# through_hole.net
KiCad netlist of a schematic drawn in EAGLE
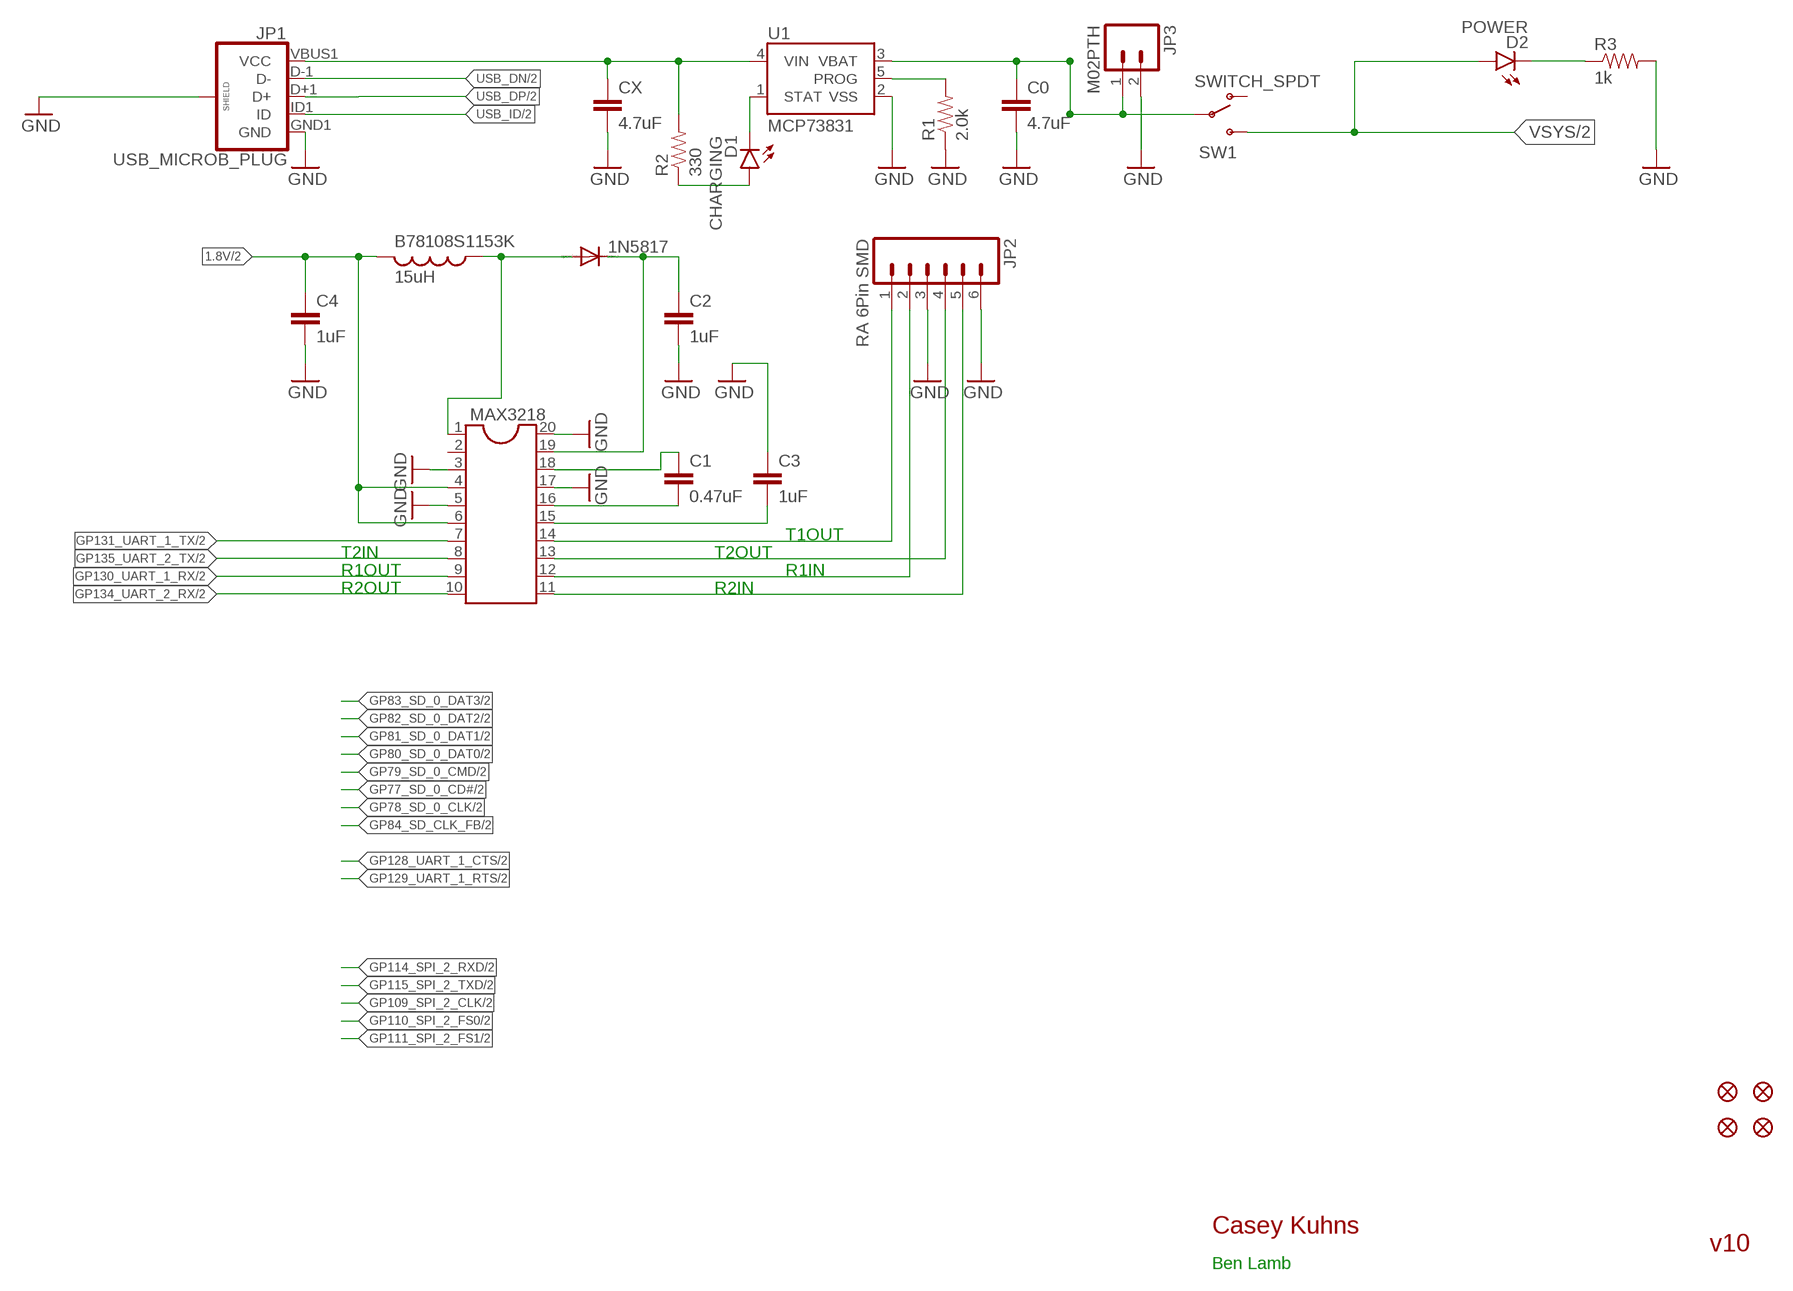
[diagram p0: schematic, sheet 1]
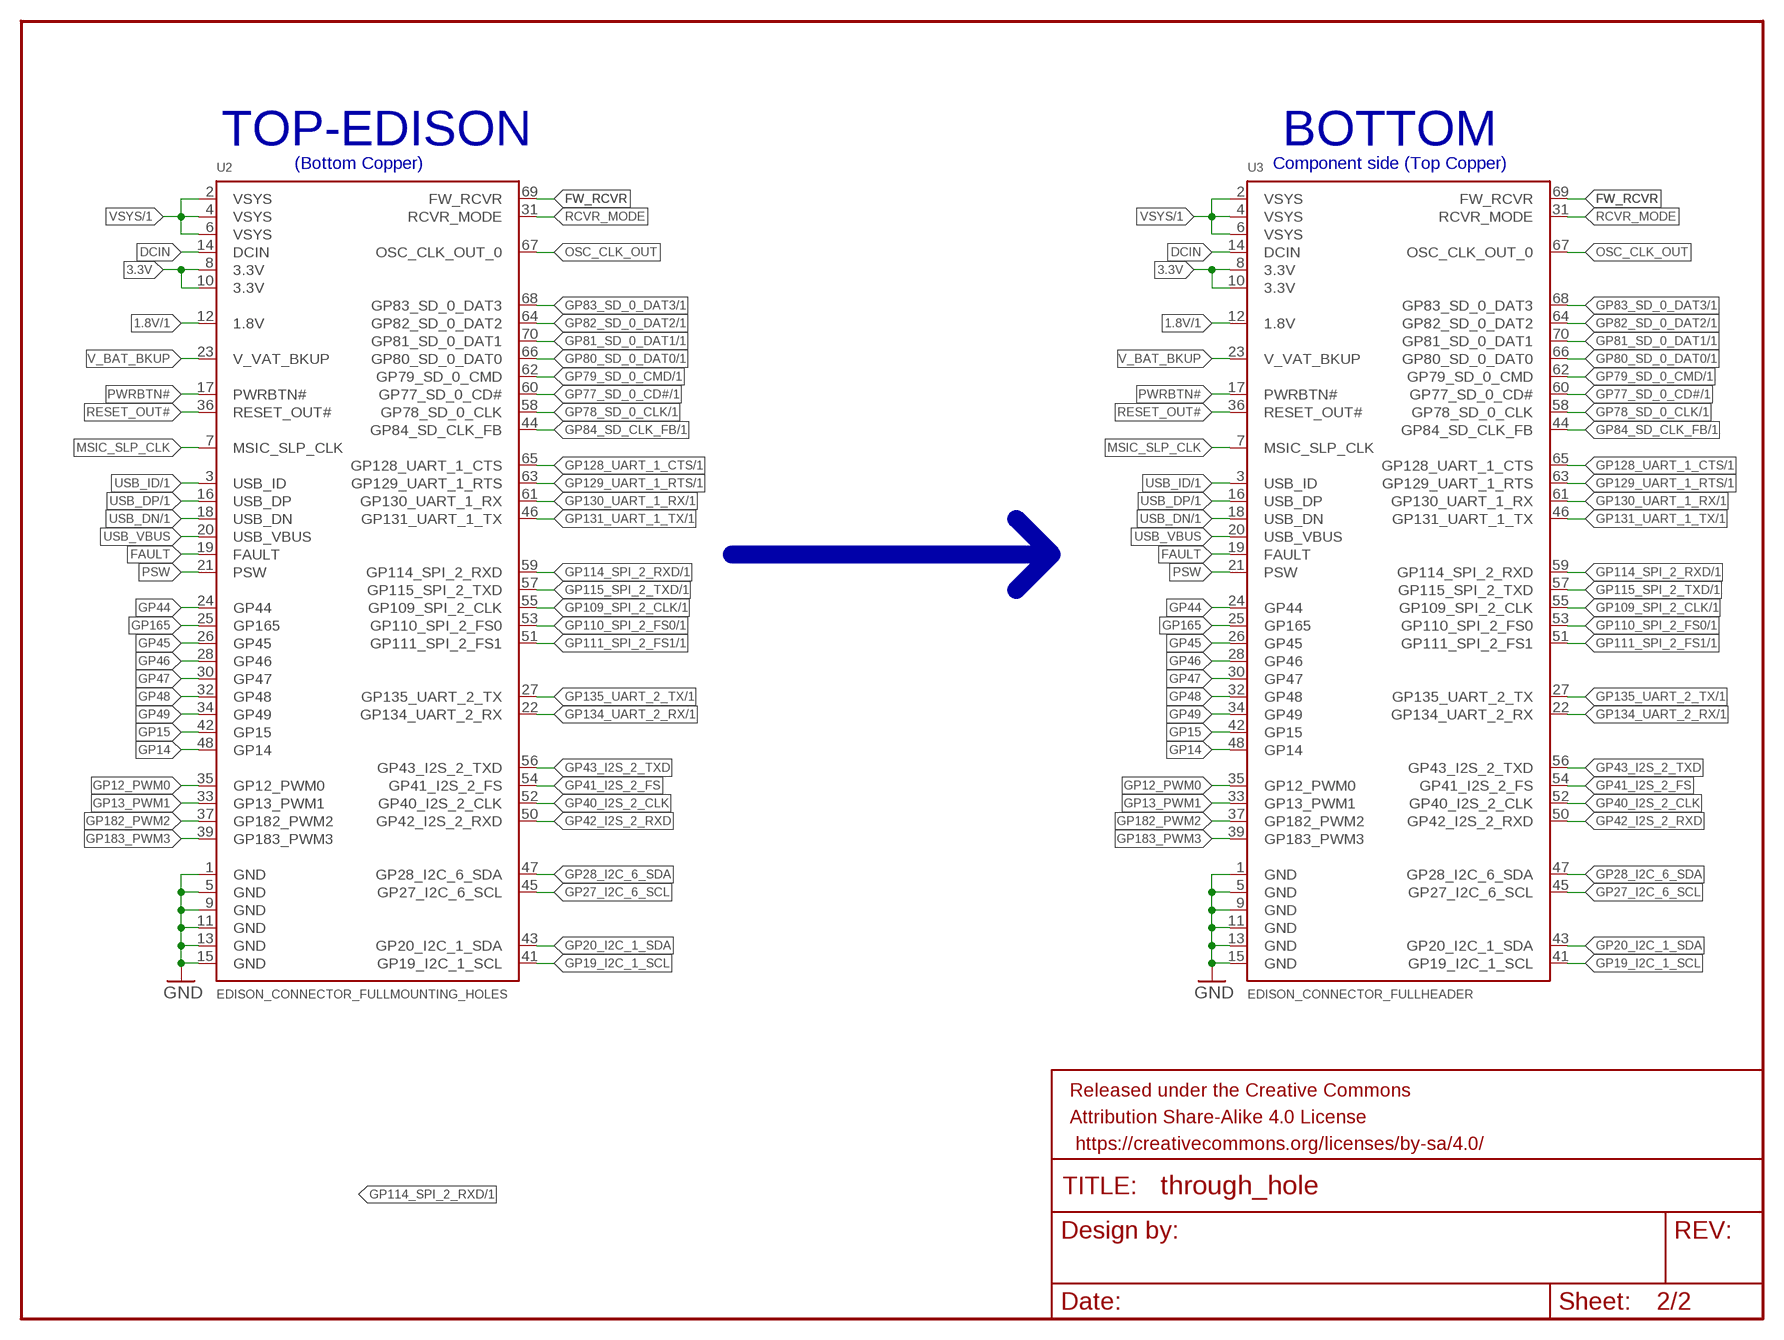
[diagram p1: schematic, sheet 2]

(export (version "E")
  (design (tool "Eeschema 10.0.6"))
  (components
    (comp (ref "FRAME2")
      (value "FRAME-LETTER")
      (footprint "eagle-import:CREATIVE_COMMONS")
      (libsource (lib "eagle-import") (part "FRAME-LETTER"))
    )
    (comp (ref "U2")
      (value "EDISON_CONNECTOR_FULLMOUNTING_HOLES")
      (footprint "eagle-import:EDISON_DAUGHTER")
      (libsource (lib "eagle-import") (part "EDISON_CONNECTOR_FULLMOUNTING_HOLES"))
    )
    (comp (ref "U3")
      (value "EDISON_CONNECTOR_FULLHEADER")
      (footprint "eagle-import:DF40C-70DP-0.4(51)")
      (libsource (lib "eagle-import") (part "EDISON_CONNECTOR_FULLHEADER"))
    )
    (comp (ref "1N5817")
      (value "DIODE-DO41-10")
      (footprint "eagle-import:DO41-10")
      (libsource (lib "eagle-import") (part "DIODE-DO41-10"))
    )
    (comp (ref "B78108S1153K")
      (value "15uH")
      (footprint "eagle-import:0207_15")
      (libsource (lib "eagle-import") (part "L-US0207/15"))
    )
    (comp (ref "C0")
      (value "4.7uF")
      (footprint "eagle-import:0603-CAP")
      (libsource (lib "eagle-import") (part "4.7UF-6.3V-10%(0603)0603"))
    )
    (comp (ref "C1")
      (value "0.47uF")
      (footprint "eagle-import:CAP-PTH-5MM")
      (libsource (lib "eagle-import") (part "CAPPTH1"))
    )
    (comp (ref "C2")
      (value "1uF")
      (footprint "eagle-import:CAP-PTH-5MM")
      (libsource (lib "eagle-import") (part "CAPPTH1"))
    )
    (comp (ref "C3")
      (value "1uF")
      (footprint "eagle-import:CAP-PTH-5MM")
      (libsource (lib "eagle-import") (part "CAPPTH1"))
    )
    (comp (ref "C4")
      (value "1uF")
      (footprint "eagle-import:CAP-PTH-5MM")
      (libsource (lib "eagle-import") (part "CAPPTH1"))
    )
    (comp (ref "CX")
      (value "4.7uF")
      (footprint "eagle-import:0603-CAP")
      (libsource (lib "eagle-import") (part "4.7UF-6.3V-10%(0603)0603"))
    )
    (comp (ref "D1")
      (value "CHARGING")
      (footprint "eagle-import:LED-0603")
      (libsource (lib "eagle-import") (part "LED-RED0603"))
    )
    (comp (ref "D2")
      (value "POWER")
      (footprint "eagle-import:LED-0603")
      (libsource (lib "eagle-import") (part "LED-BLUE0603"))
    )
    (comp (ref "FID1")
      (value "FIDUCIAL1X2")
      (footprint "eagle-import:FIDUCIAL-1X2")
      (libsource (lib "eagle-import") (part "FIDUCIAL1X2"))
    )
    (comp (ref "FID2")
      (value "FIDUCIAL1X2")
      (footprint "eagle-import:FIDUCIAL-1X2")
      (libsource (lib "eagle-import") (part "FIDUCIAL1X2"))
    )
    (comp (ref "FID3")
      (value "FIDUCIAL1X2")
      (footprint "eagle-import:FIDUCIAL-1X2")
      (libsource (lib "eagle-import") (part "FIDUCIAL1X2"))
    )
    (comp (ref "FID4")
      (value "FIDUCIAL1X2")
      (footprint "eagle-import:FIDUCIAL-1X2")
      (libsource (lib "eagle-import") (part "FIDUCIAL1X2"))
    )
    (comp (ref "JP1")
      (value "USB_MICROB_PLUG")
      (footprint "eagle-import:USB-B-MICRO-SMD_V03")
      (libsource (lib "eagle-import") (part "USB_MICROB_PLUGCONN-11752"))
    )
    (comp (ref "JP2")
      (value "RA 6Pin SMD")
      (footprint "eagle-import:1X06-SMD")
      (libsource (lib "eagle-import") (part "M06SMD"))
    )
    (comp (ref "JP3")
      (value "M02PTH")
      (footprint "eagle-import:1X02")
      (libsource (lib "eagle-import") (part "M02PTH"))
    )
    (comp (ref "MAX3218")
      (value "DIL20")
      (footprint "eagle-import:DIL20")
      (libsource (lib "eagle-import") (part "DIL20"))
    )
    (comp (ref "R1")
      (value "2.0k")
      (footprint "eagle-import:0603-RES")
      (libsource (lib "eagle-import") (part "2.0KOHM1/10W5%(0603)"))
    )
    (comp (ref "R2")
      (value "330")
      (footprint "eagle-import:0603-RES")
      (libsource (lib "eagle-import") (part "330OHM1/10W1%(0603)"))
    )
    (comp (ref "R3")
      (value "1k")
      (footprint "eagle-import:0603-RES")
      (libsource (lib "eagle-import") (part "1KOHM1/10W1%(0603)"))
    )
    (comp (ref "SW1")
      (value "SWITCH_SPDT")
      (footprint "eagle-import:KPS-1290")
      (libsource (lib "eagle-import") (part "SWITCH_SPDT"))
    )
    (comp (ref "U1")
      (value "MCP73831")
      (footprint "eagle-import:SOT23-5")
      (libsource (lib "eagle-import") (part "MCP73831"))
    )
  )
  (nets
    (net (code "1") (name "1.8V") (class "Default")
      (node (ref "B78108S1153K") (pin "2") (pinfunction "2_2") (pintype "passive"))
      (node (ref "C4") (pin "1") (pinfunction "1_1") (pintype "passive"))
      (node (ref "MAX3218") (pin "4") (pinfunction "4_4") (pintype "passive"))
      (node (ref "MAX3218") (pin "6") (pinfunction "6_6") (pintype "passive"))
      (node (ref "U2") (pin "12") (pinfunction "1.8V_12") (pintype "bidirectional"))
      (node (ref "U3") (pin "12") (pinfunction "1.8V_12") (pintype "bidirectional"))
    )
    (net (code "2") (name "3.3V") (class "Default")
      (node (ref "U2") (pin "10") (pinfunction "3.3V_10") (pintype "bidirectional"))
      (node (ref "U2") (pin "8") (pinfunction "3.3V_8") (pintype "bidirectional"))
      (node (ref "U3") (pin "10") (pinfunction "3.3V_10") (pintype "bidirectional"))
      (node (ref "U3") (pin "8") (pinfunction "3.3V_8") (pintype "bidirectional"))
    )
    (net (code "3") (name "DCIN") (class "Default")
      (node (ref "U2") (pin "14") (pinfunction "DCIN_14") (pintype "bidirectional"))
      (node (ref "U3") (pin "14") (pinfunction "DCIN_14") (pintype "bidirectional"))
    )
    (net (code "4") (name "FAULT") (class "Default")
      (node (ref "U2") (pin "19") (pinfunction "FAULT_19") (pintype "bidirectional"))
      (node (ref "U3") (pin "19") (pinfunction "FAULT_19") (pintype "bidirectional"))
    )
    (net (code "5") (name "FW_RCVR") (class "Default")
      (node (ref "U2") (pin "69") (pinfunction "FW_RCVR_69") (pintype "bidirectional"))
      (node (ref "U3") (pin "69") (pinfunction "FW_RCVR_69") (pintype "bidirectional"))
    )
    (net (code "6") (name "GND") (class "Default")
      (node (ref "C0") (pin "2") (pinfunction "2_2") (pintype "passive"))
      (node (ref "C2") (pin "2") (pinfunction "2_2") (pintype "passive"))
      (node (ref "C3") (pin "1") (pinfunction "1_1") (pintype "passive"))
      (node (ref "C4") (pin "2") (pinfunction "2_2") (pintype "passive"))
      (node (ref "CX") (pin "2") (pinfunction "2_2") (pintype "passive"))
      (node (ref "JP1") (pin "GND1") (pinfunction "GND_GND1") (pintype "bidirectional"))
      (node (ref "JP1") (pin "SHIELD1") (pinfunction "SHIELD_SHIELD1") (pintype "bidirectional"))
      (node (ref "JP1") (pin "SHIELD2") (pinfunction "SHIELD_SHIELD2") (pintype "bidirectional"))
      (node (ref "JP1") (pin "SHIELD3") (pinfunction "SHIELD_SHIELD3") (pintype "bidirectional"))
      (node (ref "JP2") (pin "3") (pinfunction "3_3") (pintype "passive"))
      (node (ref "JP2") (pin "6") (pinfunction "6_6") (pintype "passive"))
      (node (ref "JP3") (pin "2") (pinfunction "2_2") (pintype "passive"))
      (node (ref "MAX3218") (pin "17") (pinfunction "17_17") (pintype "passive"))
      (node (ref "MAX3218") (pin "20") (pinfunction "20_20") (pintype "passive"))
      (node (ref "MAX3218") (pin "3") (pinfunction "3_3") (pintype "passive"))
      (node (ref "MAX3218") (pin "5") (pinfunction "5_5") (pintype "passive"))
      (node (ref "R1") (pin "1") (pinfunction "1_1") (pintype "passive"))
      (node (ref "R3") (pin "2") (pinfunction "2_2") (pintype "passive"))
      (node (ref "U1") (pin "2") (pinfunction "VSS_2") (pintype "power_in"))
      (node (ref "U2") (pin "1") (pinfunction "GND_1") (pintype "bidirectional"))
      (node (ref "U2") (pin "11") (pinfunction "GND_11") (pintype "bidirectional"))
      (node (ref "U2") (pin "13") (pinfunction "GND_13") (pintype "bidirectional"))
      (node (ref "U2") (pin "15") (pinfunction "GND_15") (pintype "bidirectional"))
      (node (ref "U2") (pin "5") (pinfunction "GND_5") (pintype "bidirectional"))
      (node (ref "U2") (pin "9") (pinfunction "GND_9") (pintype "bidirectional"))
      (node (ref "U3") (pin "1") (pinfunction "GND_1") (pintype "bidirectional"))
      (node (ref "U3") (pin "11") (pinfunction "GND_11") (pintype "bidirectional"))
      (node (ref "U3") (pin "13") (pinfunction "GND_13") (pintype "bidirectional"))
      (node (ref "U3") (pin "15") (pinfunction "GND_15") (pintype "bidirectional"))
      (node (ref "U3") (pin "5") (pinfunction "GND_5") (pintype "bidirectional"))
      (node (ref "U3") (pin "9") (pinfunction "GND_9") (pintype "bidirectional"))
    )
    (net (code "7") (name "GP12_PWM0") (class "Default")
      (node (ref "U2") (pin "35") (pinfunction "GP12_PWM0_35") (pintype "bidirectional"))
      (node (ref "U3") (pin "35") (pinfunction "GP12_PWM0_35") (pintype "bidirectional"))
    )
    (net (code "8") (name "GP13_PWM1") (class "Default")
      (node (ref "U2") (pin "33") (pinfunction "GP13_PWM1_33") (pintype "bidirectional"))
      (node (ref "U3") (pin "33") (pinfunction "GP13_PWM1_33") (pintype "bidirectional"))
    )
    (net (code "9") (name "GP14") (class "Default")
      (node (ref "U2") (pin "48") (pinfunction "GP14_48") (pintype "bidirectional"))
      (node (ref "U3") (pin "48") (pinfunction "GP14_48") (pintype "bidirectional"))
    )
    (net (code "10") (name "GP15") (class "Default")
      (node (ref "U2") (pin "42") (pinfunction "GP15_42") (pintype "bidirectional"))
      (node (ref "U3") (pin "42") (pinfunction "GP15_42") (pintype "bidirectional"))
    )
    (net (code "11") (name "GP19_I2C_1_SCL") (class "Default")
      (node (ref "U2") (pin "41") (pinfunction "GP19_I2C_1_SCL_41") (pintype "bidirectional"))
      (node (ref "U3") (pin "41") (pinfunction "GP19_I2C_1_SCL_41") (pintype "bidirectional"))
    )
    (net (code "12") (name "GP20_I2C_1_SDA") (class "Default")
      (node (ref "U2") (pin "43") (pinfunction "GP20_I2C_1_SDA_43") (pintype "bidirectional"))
      (node (ref "U3") (pin "43") (pinfunction "GP20_I2C_1_SDA_43") (pintype "bidirectional"))
    )
    (net (code "13") (name "GP27_I2C_6_SCL") (class "Default")
      (node (ref "U2") (pin "45") (pinfunction "GP27_I2C_6_SCL_45") (pintype "bidirectional"))
      (node (ref "U3") (pin "45") (pinfunction "GP27_I2C_6_SCL_45") (pintype "bidirectional"))
    )
    (net (code "14") (name "GP28_I2C_6_SDA") (class "Default")
      (node (ref "U2") (pin "47") (pinfunction "GP28_I2C_6_SDA_47") (pintype "bidirectional"))
      (node (ref "U3") (pin "47") (pinfunction "GP28_I2C_6_SDA_47") (pintype "bidirectional"))
    )
    (net (code "15") (name "GP40_I2S_2_CLK") (class "Default")
      (node (ref "U2") (pin "52") (pinfunction "GP40_I2S_2_CLK_52") (pintype "bidirectional"))
      (node (ref "U3") (pin "52") (pinfunction "GP40_I2S_2_CLK_52") (pintype "bidirectional"))
    )
    (net (code "16") (name "GP41_I2S_2_FS") (class "Default")
      (node (ref "U2") (pin "54") (pinfunction "GP41_I2S_2_FS_54") (pintype "bidirectional"))
      (node (ref "U3") (pin "54") (pinfunction "GP41_I2S_2_FS_54") (pintype "bidirectional"))
    )
    (net (code "17") (name "GP42_I2S_2_RXD") (class "Default")
      (node (ref "U2") (pin "50") (pinfunction "GP42_I2S_2_RXD_50") (pintype "bidirectional"))
      (node (ref "U3") (pin "50") (pinfunction "GP42_I2S_2_RXD_50") (pintype "bidirectional"))
    )
    (net (code "18") (name "GP43_I2S_2_TXD") (class "Default")
      (node (ref "U2") (pin "56") (pinfunction "GP43_I2S_2_TXD_56") (pintype "bidirectional"))
      (node (ref "U3") (pin "56") (pinfunction "GP43_I2S_2_TXD_56") (pintype "bidirectional"))
    )
    (net (code "19") (name "GP44") (class "Default")
      (node (ref "U2") (pin "24") (pinfunction "GP44_24") (pintype "bidirectional"))
      (node (ref "U3") (pin "24") (pinfunction "GP44_24") (pintype "bidirectional"))
    )
    (net (code "20") (name "GP45") (class "Default")
      (node (ref "U2") (pin "26") (pinfunction "GP45_26") (pintype "bidirectional"))
      (node (ref "U3") (pin "26") (pinfunction "GP45_26") (pintype "bidirectional"))
    )
    (net (code "21") (name "GP46") (class "Default")
      (node (ref "U2") (pin "28") (pinfunction "GP46_28") (pintype "bidirectional"))
      (node (ref "U3") (pin "28") (pinfunction "GP46_28") (pintype "bidirectional"))
    )
    (net (code "22") (name "GP47") (class "Default")
      (node (ref "U2") (pin "30") (pinfunction "GP47_30") (pintype "bidirectional"))
      (node (ref "U3") (pin "30") (pinfunction "GP47_30") (pintype "bidirectional"))
    )
    (net (code "23") (name "GP48") (class "Default")
      (node (ref "U2") (pin "32") (pinfunction "GP48_32") (pintype "bidirectional"))
      (node (ref "U3") (pin "32") (pinfunction "GP48_32") (pintype "bidirectional"))
    )
    (net (code "24") (name "GP49") (class "Default")
      (node (ref "U2") (pin "34") (pinfunction "GP49_34") (pintype "bidirectional"))
      (node (ref "U3") (pin "34") (pinfunction "GP49_34") (pintype "bidirectional"))
    )
    (net (code "25") (name "GP77_SD_0_CD#") (class "Default")
      (node (ref "U2") (pin "60") (pinfunction "GP77_SD_0_CD#_60") (pintype "bidirectional"))
      (node (ref "U3") (pin "60") (pinfunction "GP77_SD_0_CD#_60") (pintype "bidirectional"))
    )
    (net (code "26") (name "GP78_SD_0_CLK") (class "Default")
      (node (ref "U2") (pin "58") (pinfunction "GP78_SD_0_CLK_58") (pintype "bidirectional"))
      (node (ref "U3") (pin "58") (pinfunction "GP78_SD_0_CLK_58") (pintype "bidirectional"))
    )
    (net (code "27") (name "GP79_SD_0_CMD") (class "Default")
      (node (ref "U2") (pin "62") (pinfunction "GP79_SD_0_CMD_62") (pintype "bidirectional"))
      (node (ref "U3") (pin "62") (pinfunction "GP79_SD_0_CMD_62") (pintype "bidirectional"))
    )
    (net (code "28") (name "GP80_SD_0_DAT0") (class "Default")
      (node (ref "U2") (pin "66") (pinfunction "GP80_SD_0_DAT0_66") (pintype "bidirectional"))
      (node (ref "U3") (pin "66") (pinfunction "GP80_SD_0_DAT0_66") (pintype "bidirectional"))
    )
    (net (code "29") (name "GP81_SD_0_DAT1") (class "Default")
      (node (ref "U2") (pin "70") (pinfunction "GP81_SD_0_DAT1_70") (pintype "bidirectional"))
      (node (ref "U3") (pin "70") (pinfunction "GP81_SD_0_DAT1_70") (pintype "bidirectional"))
    )
    (net (code "30") (name "GP82_SD_0_DAT2") (class "Default")
      (node (ref "U2") (pin "64") (pinfunction "GP82_SD_0_DAT2_64") (pintype "bidirectional"))
      (node (ref "U3") (pin "64") (pinfunction "GP82_SD_0_DAT2_64") (pintype "bidirectional"))
    )
    (net (code "31") (name "GP83_SD_0_DAT3") (class "Default")
      (node (ref "U2") (pin "68") (pinfunction "GP83_SD_0_DAT3_68") (pintype "bidirectional"))
      (node (ref "U3") (pin "68") (pinfunction "GP83_SD_0_DAT3_68") (pintype "bidirectional"))
    )
    (net (code "32") (name "GP84_SD_CLK_FB") (class "Default")
      (node (ref "U2") (pin "44") (pinfunction "GP84_SD_CLK_FB_44") (pintype "bidirectional"))
      (node (ref "U3") (pin "44") (pinfunction "GP84_SD_CLK_FB_44") (pintype "bidirectional"))
    )
    (net (code "33") (name "GP109_SPI_2_CLK") (class "Default")
      (node (ref "U2") (pin "55") (pinfunction "GP109_SPI_2_CLK_55") (pintype "bidirectional"))
      (node (ref "U3") (pin "55") (pinfunction "GP109_SPI_2_CLK_55") (pintype "bidirectional"))
    )
    (net (code "34") (name "GP110_SPI_2_FS0") (class "Default")
      (node (ref "U2") (pin "53") (pinfunction "GP110_SPI_2_FS0_53") (pintype "bidirectional"))
      (node (ref "U3") (pin "53") (pinfunction "GP110_SPI_2_FS0_53") (pintype "bidirectional"))
    )
    (net (code "35") (name "GP111_SPI_2_FS1") (class "Default")
      (node (ref "U2") (pin "51") (pinfunction "GP111_SPI_2_FS1_51") (pintype "bidirectional"))
      (node (ref "U3") (pin "51") (pinfunction "GP111_SPI_2_FS1_51") (pintype "bidirectional"))
    )
    (net (code "36") (name "GP114_SPI_2_RXD") (class "Default")
      (node (ref "U2") (pin "59") (pinfunction "GP114_SPI_2_RXD_59") (pintype "bidirectional"))
      (node (ref "U3") (pin "59") (pinfunction "GP114_SPI_2_RXD_59") (pintype "bidirectional"))
    )
    (net (code "37") (name "GP115_SPI_2_TXD") (class "Default")
      (node (ref "U2") (pin "57") (pinfunction "GP115_SPI_2_TXD_57") (pintype "bidirectional"))
      (node (ref "U3") (pin "57") (pinfunction "GP115_SPI_2_TXD_57") (pintype "bidirectional"))
    )
    (net (code "38") (name "GP128_UART_1_CTS") (class "Default")
      (node (ref "U2") (pin "65") (pinfunction "GP128_UART_1_CTS_65") (pintype "bidirectional"))
      (node (ref "U3") (pin "65") (pinfunction "GP128_UART_1_CTS_65") (pintype "bidirectional"))
    )
    (net (code "39") (name "GP129_UART_1_RTS") (class "Default")
      (node (ref "U2") (pin "63") (pinfunction "GP129_UART_1_RTS_63") (pintype "bidirectional"))
      (node (ref "U3") (pin "63") (pinfunction "GP129_UART_1_RTS_63") (pintype "bidirectional"))
    )
    (net (code "40") (name "GP130_UART_1_RX") (class "Default")
      (node (ref "MAX3218") (pin "9") (pinfunction "9_9") (pintype "passive"))
      (node (ref "U2") (pin "61") (pinfunction "GP130_UART_1_RX_61") (pintype "bidirectional"))
      (node (ref "U3") (pin "61") (pinfunction "GP130_UART_1_RX_61") (pintype "bidirectional"))
    )
    (net (code "41") (name "GP131_UART_1_TX") (class "Default")
      (node (ref "MAX3218") (pin "7") (pinfunction "7_7") (pintype "passive"))
      (node (ref "U2") (pin "46") (pinfunction "GP131_UART_1_TX_46") (pintype "bidirectional"))
      (node (ref "U3") (pin "46") (pinfunction "GP131_UART_1_TX_46") (pintype "bidirectional"))
    )
    (net (code "42") (name "GP134_UART_2_RX") (class "Default")
      (node (ref "MAX3218") (pin "10") (pinfunction "10_10") (pintype "passive"))
      (node (ref "U2") (pin "22") (pinfunction "GP134_UART_2_RX_22") (pintype "bidirectional"))
      (node (ref "U3") (pin "22") (pinfunction "GP134_UART_2_RX_22") (pintype "bidirectional"))
    )
    (net (code "43") (name "GP135_UART_2_TX") (class "Default")
      (node (ref "MAX3218") (pin "8") (pinfunction "8_8") (pintype "passive"))
      (node (ref "U2") (pin "27") (pinfunction "GP135_UART_2_TX_27") (pintype "bidirectional"))
      (node (ref "U3") (pin "27") (pinfunction "GP135_UART_2_TX_27") (pintype "bidirectional"))
    )
    (net (code "44") (name "GP165") (class "Default")
      (node (ref "U2") (pin "25") (pinfunction "GP165_25") (pintype "bidirectional"))
      (node (ref "U3") (pin "25") (pinfunction "GP165_25") (pintype "bidirectional"))
    )
    (net (code "45") (name "GP182_PWM2") (class "Default")
      (node (ref "U2") (pin "37") (pinfunction "GP182_PWM2_37") (pintype "bidirectional"))
      (node (ref "U3") (pin "37") (pinfunction "GP182_PWM2_37") (pintype "bidirectional"))
    )
    (net (code "46") (name "GP183_PWM3") (class "Default")
      (node (ref "U2") (pin "39") (pinfunction "GP183_PWM3_39") (pintype "bidirectional"))
      (node (ref "U3") (pin "39") (pinfunction "GP183_PWM3_39") (pintype "bidirectional"))
    )
    (net (code "47") (name "MSIC_SLP_CLK") (class "Default")
      (node (ref "U2") (pin "7") (pinfunction "MSIC_SLP_CLK_7") (pintype "bidirectional"))
      (node (ref "U3") (pin "7") (pinfunction "MSIC_SLP_CLK_7") (pintype "bidirectional"))
    )
    (net (code "48") (name "Net-(1N5817-PadA)") (class "Default")
      (node (ref "1N5817") (pin "A") (pinfunction "A_A") (pintype "passive"))
      (node (ref "B78108S1153K") (pin "1") (pinfunction "1_1") (pintype "passive"))
      (node (ref "MAX3218") (pin "1") (pinfunction "1_1") (pintype "passive"))
    )
    (net (code "49") (name "Net-(1N5817-PadC)") (class "Default")
      (node (ref "1N5817") (pin "C") (pinfunction "C_C") (pintype "passive"))
      (node (ref "C2") (pin "1") (pinfunction "1_1") (pintype "passive"))
      (node (ref "MAX3218") (pin "19") (pinfunction "19_19") (pintype "passive"))
    )
    (net (code "50") (name "Net-(C1-Pad1)") (class "Default")
      (node (ref "C1") (pin "1") (pinfunction "1_1") (pintype "passive"))
      (node (ref "MAX3218") (pin "18") (pinfunction "18_18") (pintype "passive"))
    )
    (net (code "51") (name "Net-(C1-Pad2)") (class "Default")
      (node (ref "C1") (pin "2") (pinfunction "2_2") (pintype "passive"))
      (node (ref "MAX3218") (pin "16") (pinfunction "16_16") (pintype "passive"))
    )
    (net (code "52") (name "Net-(C3-Pad2)") (class "Default")
      (node (ref "C3") (pin "2") (pinfunction "2_2") (pintype "passive"))
      (node (ref "MAX3218") (pin "15") (pinfunction "15_15") (pintype "passive"))
    )
    (net (code "53") (name "Net-(D1-PadA)") (class "Default")
      (node (ref "D1") (pin "A") (pinfunction "A_A") (pintype "passive"))
      (node (ref "R2") (pin "1") (pinfunction "1_1") (pintype "passive"))
    )
    (net (code "54") (name "Net-(D2-PadC)") (class "Default")
      (node (ref "D2") (pin "C") (pinfunction "C_C") (pintype "passive"))
      (node (ref "R3") (pin "1") (pinfunction "1_1") (pintype "passive"))
    )
    (net (code "55") (name "Net-(JP1-VCC)") (class "Default")
      (node (ref "CX") (pin "1") (pinfunction "1_1") (pintype "passive"))
      (node (ref "JP1") (pin "VBUS1") (pinfunction "VCC_VBUS1") (pintype "bidirectional"))
      (node (ref "R2") (pin "2") (pinfunction "2_2") (pintype "passive"))
      (node (ref "U1") (pin "4") (pinfunction "VIN_4") (pintype "power_in"))
    )
    (net (code "56") (name "Net-(JP2-Pad1)") (class "Default")
      (node (ref "JP2") (pin "1") (pinfunction "1_1") (pintype "passive"))
      (node (ref "MAX3218") (pin "14") (pinfunction "14_14") (pintype "passive"))
    )
    (net (code "57") (name "Net-(JP2-Pad2)") (class "Default")
      (node (ref "JP2") (pin "2") (pinfunction "2_2") (pintype "passive"))
      (node (ref "MAX3218") (pin "12") (pinfunction "12_12") (pintype "passive"))
    )
    (net (code "58") (name "Net-(JP2-Pad4)") (class "Default")
      (node (ref "JP2") (pin "4") (pinfunction "4_4") (pintype "passive"))
      (node (ref "MAX3218") (pin "13") (pinfunction "13_13") (pintype "passive"))
    )
    (net (code "59") (name "Net-(JP2-Pad5)") (class "Default")
      (node (ref "JP2") (pin "5") (pinfunction "5_5") (pintype "passive"))
      (node (ref "MAX3218") (pin "11") (pinfunction "11_11") (pintype "passive"))
    )
    (net (code "60") (name "Net-(U1-PROG)") (class "Default")
      (node (ref "R1") (pin "2") (pinfunction "2_2") (pintype "passive"))
      (node (ref "U1") (pin "5") (pinfunction "PROG_5") (pintype "input"))
    )
    (net (code "61") (name "Net-(U1-STAT)") (class "Default")
      (node (ref "D1") (pin "C") (pinfunction "C_C") (pintype "passive"))
      (node (ref "U1") (pin "1") (pinfunction "STAT_1") (pintype "output"))
    )
    (net (code "62") (name "Net-(U1-VBAT)") (class "Default")
      (node (ref "C0") (pin "1") (pinfunction "1_1") (pintype "passive"))
      (node (ref "JP3") (pin "1") (pinfunction "1_1") (pintype "passive"))
      (node (ref "SW1") (pin "P") (pinfunction "P_P") (pintype "passive"))
      (node (ref "U1") (pin "3") (pinfunction "VBAT_3") (pintype "power_in"))
    )
    (net (code "63") (name "OSC_CLK_OUT") (class "Default")
      (node (ref "U2") (pin "67") (pinfunction "OSC_CLK_OUT_0_67") (pintype "bidirectional"))
      (node (ref "U3") (pin "67") (pinfunction "OSC_CLK_OUT_0_67") (pintype "bidirectional"))
    )
    (net (code "64") (name "PSW") (class "Default")
      (node (ref "U2") (pin "21") (pinfunction "PSW_21") (pintype "bidirectional"))
      (node (ref "U3") (pin "21") (pinfunction "PSW_21") (pintype "bidirectional"))
    )
    (net (code "65") (name "PWRBTN#") (class "Default")
      (node (ref "U2") (pin "17") (pinfunction "PWRBTN#_17") (pintype "bidirectional"))
      (node (ref "U3") (pin "17") (pinfunction "PWRBTN#_17") (pintype "bidirectional"))
    )
    (net (code "66") (name "RCVR_MODE") (class "Default")
      (node (ref "U2") (pin "31") (pinfunction "RCVR_MODE_31") (pintype "bidirectional"))
      (node (ref "U3") (pin "31") (pinfunction "RCVR_MODE_31") (pintype "bidirectional"))
    )
    (net (code "67") (name "RESET_OUT#") (class "Default")
      (node (ref "U2") (pin "36") (pinfunction "RESET_OUT#_36") (pintype "bidirectional"))
      (node (ref "U3") (pin "36") (pinfunction "RESET_OUT#_36") (pintype "bidirectional"))
    )
    (net (code "68") (name "USB_DN") (class "Default")
      (node (ref "JP1") (pin "D-1") (pinfunction "D-_D-1") (pintype "bidirectional"))
      (node (ref "U2") (pin "18") (pinfunction "USB_DN_18") (pintype "bidirectional"))
      (node (ref "U3") (pin "18") (pinfunction "USB_DN_18") (pintype "bidirectional"))
    )
    (net (code "69") (name "USB_DP") (class "Default")
      (node (ref "JP1") (pin "D+1") (pinfunction "D+_D+1") (pintype "bidirectional"))
      (node (ref "U2") (pin "16") (pinfunction "USB_DP_16") (pintype "bidirectional"))
      (node (ref "U3") (pin "16") (pinfunction "USB_DP_16") (pintype "bidirectional"))
    )
    (net (code "70") (name "USB_ID") (class "Default")
      (node (ref "JP1") (pin "ID1") (pinfunction "ID_ID1") (pintype "bidirectional"))
      (node (ref "U2") (pin "3") (pinfunction "USB_ID_3") (pintype "bidirectional"))
      (node (ref "U3") (pin "3") (pinfunction "USB_ID_3") (pintype "bidirectional"))
    )
    (net (code "71") (name "USB_VBUS") (class "Default")
      (node (ref "U2") (pin "20") (pinfunction "USB_VBUS_20") (pintype "bidirectional"))
      (node (ref "U3") (pin "20") (pinfunction "USB_VBUS_20") (pintype "bidirectional"))
    )
    (net (code "72") (name "VSYS") (class "Default")
      (node (ref "D2") (pin "A") (pinfunction "A_A") (pintype "passive"))
      (node (ref "SW1") (pin "S") (pinfunction "S_S") (pintype "passive"))
      (node (ref "U2") (pin "2") (pinfunction "VSYS_2") (pintype "bidirectional"))
      (node (ref "U2") (pin "4") (pinfunction "VSYS_4") (pintype "bidirectional"))
      (node (ref "U2") (pin "6") (pinfunction "VSYS_6") (pintype "bidirectional"))
      (node (ref "U3") (pin "2") (pinfunction "VSYS_2") (pintype "bidirectional"))
      (node (ref "U3") (pin "4") (pinfunction "VSYS_4") (pintype "bidirectional"))
      (node (ref "U3") (pin "6") (pinfunction "VSYS_6") (pintype "bidirectional"))
    )
    (net (code "73") (name "V_BAT_BKUP") (class "Default")
      (node (ref "U2") (pin "23") (pinfunction "V_VAT_BKUP_23") (pintype "bidirectional"))
      (node (ref "U3") (pin "23") (pinfunction "V_VAT_BKUP_23") (pintype "bidirectional"))
    )
    (net (code "74") (name "unconnected-(MAX3218-Pad2)") (class "Default")
      (node (ref "MAX3218") (pin "2") (pinfunction "2_2") (pintype "passive"))
    )
    (net (code "75") (name "unconnected-(SW1-PadO)") (class "Default")
      (node (ref "SW1") (pin "O") (pinfunction "O_O") (pintype "passive"))
    )
  )
)
